# link_t.net
KiCad netlist of a schematic drawn in Altium Designer
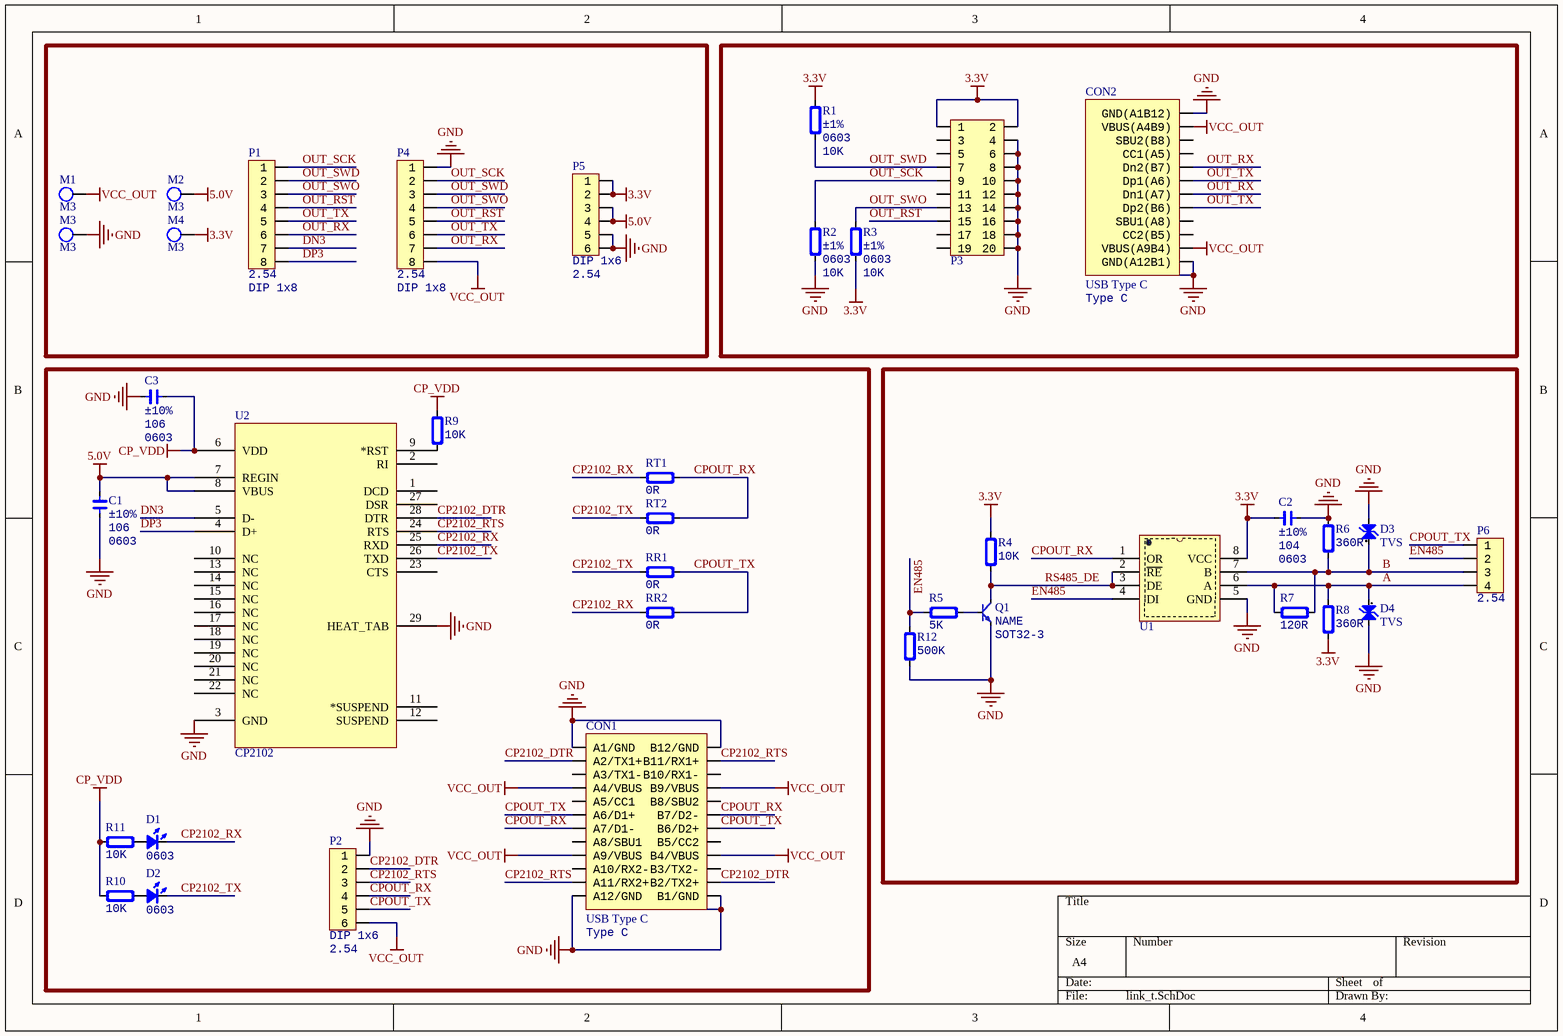
[diagram p0: link_t.SchDoc]

(export (version "E")
  (design (tool "Eeschema 10.0.6"))
  (components
    (comp (ref "C1")
      (value "106")
      (footprint "CAP_0603")
      (description "Capacitor")
      (fields (field (name "NOTE") "±10%") (field (name "TYPE") "0603") (field (name "Comment") "C0603"))
      (libsource (lib "") (part "Cap_0603_1"))
    )
    (comp (ref "C2")
      (value "104")
      (footprint "CAP_0603")
      (description "Capacitor")
      (fields (field (name "NOTE") "±10%") (field (name "TYPE") "0603") (field (name "Comment") "C0603"))
      (libsource (lib "") (part "Cap_0603_2"))
    )
    (comp (ref "C3")
      (value "106")
      (footprint "CAP_0603")
      (description "Capacitor")
      (fields (field (name "NOTE") "±10%") (field (name "TYPE") "0603") (field (name "Comment") "C0603"))
      (libsource (lib "Integrated_Library") (part "Cap_0603"))
    )
    (comp (ref "CON1")
      (value "USB Type C")
      (footprint "USB_TypeC_SMD_24P")
      (description "USB")
      (fields (field (name "ALTIUM_VALUE") "Type C"))
      (libsource (lib "Integrated_Library") (part "USB_TypeC"))
    )
    (comp (ref "CON2")
      (value "USB Type C")
      (footprint "USB_TypeC_SMD_16P")
      (description "USB")
      (fields (field (name "ALTIUM_VALUE") "Type C"))
      (libsource (lib "Integrated_Library") (part "USB_TypeC_16P"))
    )
    (comp (ref "D1")
      (value "D0603")
      (footprint "LED_0603_RED")
      (description "LED")
      (fields (field (name "TYPE") "0603"))
      (libsource (lib "Integrated_Library") (part "LED_0603"))
    )
    (comp (ref "D2")
      (value "D0603")
      (footprint "LED_0603_RED")
      (description "LED")
      (fields (field (name "TYPE") "0603"))
      (libsource (lib "Integrated_Library") (part "LED_0603"))
    )
    (comp (ref "D3")
      (value "TVS")
      (footprint "LED_0603_YELLOW")
      (description "静电保护二极管,VRWM=5V.IPP=9.4A")
      (libsource (lib "MxM_Library") (part "ESD LESD5D5.0CT1G"))
    )
    (comp (ref "D4")
      (value "TVS")
      (footprint "LED_0603_YELLOW")
      (description "静电保护二极管,VRWM=5V.IPP=9.4A")
      (libsource (lib "MxM_Library") (part "ESD LESD5D5.0CT1G"))
    )
    (comp (ref "M1")
      (value "M3")
      (footprint "M3")
      (description "M3 Nut")
      (libsource (lib "Integrated_Library") (part "M3"))
    )
    (comp (ref "M2")
      (value "M3")
      (footprint "M3")
      (description "M3 Nut")
      (libsource (lib "Integrated_Library") (part "M3"))
    )
    (comp (ref "M3")
      (value "M3")
      (footprint "M3")
      (description "M3 Nut")
      (libsource (lib "Integrated_Library") (part "M3"))
    )
    (comp (ref "M4")
      (value "M3")
      (footprint "M3")
      (description "M3 Nut")
      (libsource (lib "Integrated_Library") (part "M3"))
    )
    (comp (ref "P1")
      (value "2.54")
      (footprint "HDR1x8_TOP")
      (description "Header Top")
      (fields (field (name "TYPE") "DIP 1x8") (field (name "Comment") "HDR1x8"))
      (libsource (lib "Integrated_Library") (part "HDR1x8_2.54TOP"))
    )
    (comp (ref "P2")
      (value "2.54")
      (footprint "HDR1x6_TOP")
      (description "Header Top")
      (fields (field (name "TYPE") "DIP 1x6") (field (name "Comment") "HDR1x6"))
      (libsource (lib "Integrated_Library") (part "HDR1x6_2.54TOP"))
    )
    (comp (ref "P3")
      (value "HDR2x10")
      (footprint "PCB_Special:JN_STM_20PIN")
      (description "Header")
      (libsource (lib "Integrated_Library") (part "HDR2x10_2.54"))
    )
    (comp (ref "P4")
      (value "2.54")
      (footprint "HDR1X8_H")
      (description "Header Top")
      (fields (field (name "TYPE") "DIP 1x8") (field (name "Comment") "HDR1x8"))
      (libsource (lib "Integrated_Library") (part "HDR1x8_2.54TOP"))
    )
    (comp (ref "P5")
      (value "2.54")
      (footprint "HDR1x6_TOP")
      (description "Header Top")
      (fields (field (name "TYPE") "DIP 1x6") (field (name "Comment") "HDR1x6"))
      (libsource (lib "Integrated_Library") (part "HDR1x6_2.54TOP"))
    )
    (comp (ref "P6")
      (value "2.54")
      (footprint "HDR1x4_TOP")
      (description "Header Top")
      (fields (field (name "Comment") "HDR1x4"))
      (libsource (lib "Integrated_Library") (part "HDR1x4_2.54TOP"))
    )
    (comp (ref "Q1")
      (value "NAME")
      (footprint "SOT23-3")
      (description "Transistor")
      (fields (field (name "TYPE") "SOT32-3"))
      (libsource (lib "Integrated_Library") (part "BJT_NPN"))
    )
    (comp (ref "R1")
      (value "10K")
      (footprint "RES_0603")
      (description "Resistor")
      (fields (field (name "NOTE") "±1%") (field (name "TYPE") "0603") (field (name "Comment") "R0603"))
      (libsource (lib "Integrated_Library") (part "Res_0603"))
    )
    (comp (ref "R2")
      (value "10K")
      (footprint "RES_0603")
      (description "Resistor")
      (fields (field (name "NOTE") "±1%") (field (name "TYPE") "0603") (field (name "Comment") "R0603"))
      (libsource (lib "Integrated_Library") (part "Res_0603"))
    )
    (comp (ref "R3")
      (value "10K")
      (footprint "RES_0603")
      (description "Resistor")
      (fields (field (name "NOTE") "±1%") (field (name "TYPE") "0603") (field (name "Comment") "R0603"))
      (libsource (lib "Integrated_Library") (part "Res_0603"))
    )
    (comp (ref "R4")
      (value "10K")
      (footprint "RES_0603")
      (description "Resistor")
      (fields (field (name "Comment") "R0603"))
      (libsource (lib "Integrated_Library") (part "Res_0603"))
    )
    (comp (ref "R5")
      (value "5K")
      (footprint "RES_0603")
      (description "Resistor")
      (fields (field (name "Comment") "R0603"))
      (libsource (lib "Integrated_Library") (part "Res_0603"))
    )
    (comp (ref "R6")
      (value "360R")
      (footprint "RES_0603")
      (description "Resistor")
      (fields (field (name "Comment") "R0603"))
      (libsource (lib "Integrated_Library") (part "Res_0603"))
    )
    (comp (ref "R7")
      (value "120R")
      (footprint "RES_0603")
      (description "Resistor")
      (fields (field (name "Comment") "R0603"))
      (libsource (lib "Integrated_Library") (part "Res_0603"))
    )
    (comp (ref "R8")
      (value "360R")
      (footprint "RES_0603")
      (description "Resistor")
      (fields (field (name "Comment") "R0603"))
      (libsource (lib "Integrated_Library") (part "Res_0603"))
    )
    (comp (ref "R9")
      (value "10K")
      (footprint "RES_0603")
      (description "Resistor")
      (fields (field (name "Comment") "R0603"))
      (libsource (lib "Integrated_Library") (part "Res_0603"))
    )
    (comp (ref "R10")
      (value "10K")
      (footprint "RES_0603")
      (description "Resistor")
      (fields (field (name "Comment") "R0603"))
      (libsource (lib "Integrated_Library") (part "Res_0603"))
    )
    (comp (ref "R11")
      (value "10K")
      (footprint "RES_0603")
      (description "Resistor")
      (fields (field (name "Comment") "R0603"))
      (libsource (lib "Integrated_Library") (part "Res_0603"))
    )
    (comp (ref "R12")
      (value "500K")
      (footprint "RES_0603")
      (description "Resistor")
      (fields (field (name "Comment") "R0603"))
      (libsource (lib "Integrated_Library") (part "Res_0603"))
    )
    (comp (ref "RR1")
      (value "0R")
      (footprint "RES_0603")
      (description "Resistor")
      (fields (field (name "Comment") "R0603"))
      (libsource (lib "Integrated_Library") (part "Res_0603"))
    )
    (comp (ref "RR2")
      (value "0R")
      (footprint "RES_0603")
      (description "Resistor")
      (fields (field (name "Comment") "R0603"))
      (libsource (lib "Integrated_Library") (part "Res_0603"))
    )
    (comp (ref "RT1")
      (value "0R")
      (footprint "RES_0603")
      (description "Resistor")
      (fields (field (name "Comment") "R0603"))
      (libsource (lib "Integrated_Library") (part "Res_0603"))
    )
    (comp (ref "RT2")
      (value "0R")
      (footprint "RES_0603")
      (description "Resistor")
      (fields (field (name "Comment") "R0603"))
      (libsource (lib "Integrated_Library") (part "Res_0603"))
    )
    (comp (ref "U1")
      (value "SP3485")
      (footprint "SOP8")
      (description "半双工收发器")
      (libsource (lib "MxM_Library") (part "SP3485"))
    )
    (comp (ref "U2")
      (value "CP2102")
      (footprint "rice_mill_esp32:QFN-28")
      (description "USB转TTL")
      (libsource (lib "mLib") (part "CP2102"))
    )
  )
  (nets
    (net (code "1") (name "/A") (class "Default")
      (node (ref "D4") (pin "1") (pinfunction "A_1") (pintype "passive"))
      (node (ref "P6") (pin "4") (pinfunction "4_4") (pintype "passive"))
      (node (ref "R7") (pin "1") (pinfunction "1_1") (pintype "passive"))
      (node (ref "R8") (pin "2") (pinfunction "2_2") (pintype "passive"))
      (node (ref "U1") (pin "6") (pinfunction "A_6") (pintype "passive"))
    )
    (net (code "2") (name "/B") (class "Default")
      (node (ref "D3") (pin "1") (pinfunction "A_1") (pintype "passive"))
      (node (ref "P6") (pin "3") (pinfunction "3_3") (pintype "passive"))
      (node (ref "R6") (pin "1") (pinfunction "1_1") (pintype "passive"))
      (node (ref "R7") (pin "2") (pinfunction "2_2") (pintype "passive"))
      (node (ref "U1") (pin "7") (pinfunction "B_7") (pintype "passive"))
    )
    (net (code "3") (name "/CP2102_DTR") (class "Default")
      (node (ref "CON1") (pin "A2") (pinfunction "A2/TX1+_A2") (pintype "passive"))
      (node (ref "CON1") (pin "B2") (pinfunction "B2/TX2+_B2") (pintype "passive"))
      (node (ref "P2") (pin "2") (pinfunction "2_2") (pintype "passive"))
      (node (ref "U2") (pin "28") (pinfunction "DTR_28") (pintype "passive"))
    )
    (net (code "4") (name "/CP2102_RTS") (class "Default")
      (node (ref "CON1") (pin "A11") (pinfunction "A11/RX2+_A11") (pintype "passive"))
      (node (ref "CON1") (pin "B11") (pinfunction "B11/RX1+_B11") (pintype "passive"))
      (node (ref "P2") (pin "3") (pinfunction "3_3") (pintype "passive"))
      (node (ref "U2") (pin "24") (pinfunction "RTS_24") (pintype "passive"))
    )
    (net (code "5") (name "/CP2102_RX") (class "Default")
      (node (ref "D1") (pin "2") (pinfunction "K_2") (pintype "passive"))
      (node (ref "RR2") (pin "2") (pinfunction "2_2") (pintype "passive"))
      (node (ref "RT1") (pin "2") (pinfunction "2_2") (pintype "passive"))
      (node (ref "U2") (pin "25") (pinfunction "RXD_25") (pintype "passive"))
    )
    (net (code "6") (name "/CP2102_TX") (class "Default")
      (node (ref "D2") (pin "2") (pinfunction "K_2") (pintype "passive"))
      (node (ref "RR1") (pin "2") (pinfunction "2_2") (pintype "passive"))
      (node (ref "RT2") (pin "2") (pinfunction "2_2") (pintype "passive"))
      (node (ref "U2") (pin "26") (pinfunction "TXD_26") (pintype "passive"))
    )
    (net (code "7") (name "/CPOUT_RX") (class "Default")
      (node (ref "CON1") (pin "A7") (pinfunction "A7/D1-_A7") (pintype "passive"))
      (node (ref "CON1") (pin "B7") (pinfunction "B7/D2-_B7") (pintype "passive"))
      (node (ref "P2") (pin "4") (pinfunction "4_4") (pintype "passive"))
      (node (ref "RT1") (pin "1") (pinfunction "1_1") (pintype "passive"))
      (node (ref "RT2") (pin "1") (pinfunction "1_1") (pintype "passive"))
      (node (ref "U1") (pin "1") (pinfunction "OR_1") (pintype "passive"))
    )
    (net (code "8") (name "/CPOUT_TX") (class "Default")
      (node (ref "CON1") (pin "A6") (pinfunction "A6/D1+_A6") (pintype "passive"))
      (node (ref "CON1") (pin "B6") (pinfunction "B6/D2+_B6") (pintype "passive"))
      (node (ref "P2") (pin "5") (pinfunction "5_5") (pintype "passive"))
      (node (ref "P6") (pin "1") (pinfunction "1_1") (pintype "passive"))
      (node (ref "RR1") (pin "1") (pinfunction "1_1") (pintype "passive"))
      (node (ref "RR2") (pin "1") (pinfunction "1_1") (pintype "passive"))
    )
    (net (code "9") (name "/DN3") (class "Default")
      (node (ref "P1") (pin "7") (pinfunction "7_7") (pintype "passive"))
      (node (ref "U2") (pin "5") (pinfunction "D-_5") (pintype "passive"))
    )
    (net (code "10") (name "/DP3") (class "Default")
      (node (ref "P1") (pin "8") (pinfunction "8_8") (pintype "passive"))
      (node (ref "U2") (pin "4") (pinfunction "D+_4") (pintype "passive"))
    )
    (net (code "11") (name "/EN485") (class "Default")
      (node (ref "P6") (pin "2") (pinfunction "2_2") (pintype "passive"))
      (node (ref "R12") (pin "1") (pinfunction "1_1") (pintype "passive"))
      (node (ref "R5") (pin "2") (pinfunction "2_2") (pintype "passive"))
      (node (ref "U1") (pin "4") (pinfunction "DI_4") (pintype "passive"))
    )
    (net (code "12") (name "/OUT_RST") (class "Default")
      (node (ref "P1") (pin "4") (pinfunction "4_4") (pintype "passive"))
      (node (ref "P3") (pin "15") (pinfunction "15_15") (pintype "passive"))
      (node (ref "P4") (pin "5") (pinfunction "5_5") (pintype "passive"))
    )
    (net (code "13") (name "/OUT_RX") (class "Default")
      (node (ref "CON2") (pin "A7") (pinfunction "Dn1(A7)_A7") (pintype "passive"))
      (node (ref "CON2") (pin "B7") (pinfunction "Dn2(B7)_B7") (pintype "passive"))
      (node (ref "P1") (pin "6") (pinfunction "6_6") (pintype "passive"))
      (node (ref "P4") (pin "7") (pinfunction "7_7") (pintype "passive"))
    )
    (net (code "14") (name "/OUT_SCK") (class "Default")
      (node (ref "P1") (pin "1") (pinfunction "1_1") (pintype "passive"))
      (node (ref "P3") (pin "9") (pinfunction "9_9") (pintype "passive"))
      (node (ref "P4") (pin "2") (pinfunction "2_2") (pintype "passive"))
      (node (ref "R2") (pin "2") (pinfunction "2_2") (pintype "passive"))
    )
    (net (code "15") (name "/OUT_SWD") (class "Default")
      (node (ref "P1") (pin "2") (pinfunction "2_2") (pintype "passive"))
      (node (ref "P3") (pin "7") (pinfunction "7_7") (pintype "passive"))
      (node (ref "P4") (pin "3") (pinfunction "3_3") (pintype "passive"))
      (node (ref "R1") (pin "2") (pinfunction "2_2") (pintype "passive"))
    )
    (net (code "16") (name "/OUT_SWO") (class "Default")
      (node (ref "P1") (pin "3") (pinfunction "3_3") (pintype "passive"))
      (node (ref "P3") (pin "13") (pinfunction "13_13") (pintype "passive"))
      (node (ref "P4") (pin "4") (pinfunction "4_4") (pintype "passive"))
      (node (ref "R3") (pin "2") (pinfunction "2_2") (pintype "passive"))
    )
    (net (code "17") (name "/OUT_TX") (class "Default")
      (node (ref "CON2") (pin "A6") (pinfunction "Dp1(A6)_A6") (pintype "passive"))
      (node (ref "CON2") (pin "B6") (pinfunction "Dp2(B6)_B6") (pintype "passive"))
      (node (ref "P1") (pin "5") (pinfunction "5_5") (pintype "passive"))
      (node (ref "P4") (pin "6") (pinfunction "6_6") (pintype "passive"))
    )
    (net (code "18") (name "/RS485_DE") (class "Default")
      (node (ref "Q1") (pin "3") (pinfunction "C_3") (pintype "passive"))
      (node (ref "R4") (pin "2") (pinfunction "2_2") (pintype "passive"))
      (node (ref "U1") (pin "2") (pinfunction "~{RE}_2") (pintype "passive"))
      (node (ref "U1") (pin "3") (pinfunction "DE_3") (pintype "passive"))
    )
    (net (code "19") (name "3.3V") (class "Default")
      (node (ref "C2") (pin "2") (pinfunction "2_2") (pintype "passive"))
      (node (ref "M4") (pin "1") (pinfunction "1_1") (pintype "passive"))
      (node (ref "P3") (pin "1") (pinfunction "1_1") (pintype "passive"))
      (node (ref "P3") (pin "2") (pinfunction "2_2") (pintype "passive"))
      (node (ref "P5") (pin "1") (pinfunction "1_1") (pintype "passive"))
      (node (ref "P5") (pin "2") (pinfunction "2_2") (pintype "passive"))
      (node (ref "R1") (pin "1") (pinfunction "1_1") (pintype "passive"))
      (node (ref "R3") (pin "1") (pinfunction "1_1") (pintype "passive"))
      (node (ref "R4") (pin "1") (pinfunction "1_1") (pintype "passive"))
      (node (ref "R8") (pin "1") (pinfunction "1_1") (pintype "passive"))
      (node (ref "U1") (pin "8") (pinfunction "VCC_8") (pintype "passive"))
    )
    (net (code "20") (name "5.0V") (class "Default")
      (node (ref "C1") (pin "2") (pinfunction "2_2") (pintype "passive"))
      (node (ref "M2") (pin "1") (pinfunction "1_1") (pintype "passive"))
      (node (ref "P5") (pin "3") (pinfunction "3_3") (pintype "passive"))
      (node (ref "P5") (pin "4") (pinfunction "4_4") (pintype "passive"))
      (node (ref "U2") (pin "7") (pinfunction "REGIN_7") (pintype "passive"))
      (node (ref "U2") (pin "8") (pinfunction "VBUS_8") (pintype "passive"))
    )
    (net (code "21") (name "CP_VDD") (class "Default")
      (node (ref "C3") (pin "2") (pinfunction "2_2") (pintype "passive"))
      (node (ref "R10") (pin "1") (pinfunction "1_1") (pintype "passive"))
      (node (ref "R11") (pin "1") (pinfunction "1_1") (pintype "passive"))
      (node (ref "R9") (pin "2") (pinfunction "2_2") (pintype "passive"))
      (node (ref "U2") (pin "6") (pinfunction "VDD_6") (pintype "passive"))
    )
    (net (code "22") (name "GND") (class "Default")
      (node (ref "C1") (pin "1") (pinfunction "1_1") (pintype "passive"))
      (node (ref "C2") (pin "1") (pinfunction "1_1") (pintype "passive"))
      (node (ref "C3") (pin "1") (pinfunction "1_1") (pintype "passive"))
      (node (ref "CON1") (pin "0") (pinfunction "SH_0") (pintype "passive"))
      (node (ref "CON1") (pin "A1") (pinfunction "A1/GND_A1") (pintype "passive"))
      (node (ref "CON1") (pin "A12") (pinfunction "A12/GND_A12") (pintype "passive"))
      (node (ref "CON1") (pin "B1") (pinfunction "B1/GND_B1") (pintype "passive"))
      (node (ref "CON1") (pin "B12") (pinfunction "B12/GND_B12") (pintype "passive"))
      (node (ref "CON2") (pin "0") (pinfunction "SH_0") (pintype "passive"))
      (node (ref "CON2") (pin "A12B1") (pinfunction "GND(A12B1)_A12B1") (pintype "passive"))
      (node (ref "CON2") (pin "A1B12") (pinfunction "GND(A1B12)_A1B12") (pintype "passive"))
      (node (ref "D3") (pin "2") (pinfunction "K_2") (pintype "passive"))
      (node (ref "D4") (pin "2") (pinfunction "K_2") (pintype "passive"))
      (node (ref "M3") (pin "1") (pinfunction "1_1") (pintype "passive"))
      (node (ref "P2") (pin "1") (pinfunction "1_1") (pintype "passive"))
      (node (ref "P3") (pin "10") (pinfunction "10_10") (pintype "passive"))
      (node (ref "P3") (pin "12") (pinfunction "12_12") (pintype "passive"))
      (node (ref "P3") (pin "14") (pinfunction "14_14") (pintype "passive"))
      (node (ref "P3") (pin "16") (pinfunction "16_16") (pintype "passive"))
      (node (ref "P3") (pin "18") (pinfunction "18_18") (pintype "passive"))
      (node (ref "P3") (pin "20") (pinfunction "20_20") (pintype "passive"))
      (node (ref "P3") (pin "4") (pinfunction "4_4") (pintype "passive"))
      (node (ref "P3") (pin "6") (pinfunction "6_6") (pintype "passive"))
      (node (ref "P3") (pin "8") (pinfunction "8_8") (pintype "passive"))
      (node (ref "P4") (pin "1") (pinfunction "1_1") (pintype "passive"))
      (node (ref "P5") (pin "5") (pinfunction "5_5") (pintype "passive"))
      (node (ref "P5") (pin "6") (pinfunction "6_6") (pintype "passive"))
      (node (ref "Q1") (pin "2") (pinfunction "E_2") (pintype "passive"))
      (node (ref "R12") (pin "2") (pinfunction "2_2") (pintype "passive"))
      (node (ref "R2") (pin "1") (pinfunction "1_1") (pintype "passive"))
      (node (ref "R6") (pin "2") (pinfunction "2_2") (pintype "passive"))
      (node (ref "U1") (pin "5") (pinfunction "GND_5") (pintype "passive"))
      (node (ref "U2") (pin "29") (pinfunction "HEAT_TAB_29") (pintype "passive"))
      (node (ref "U2") (pin "3") (pinfunction "GND_3") (pintype "passive"))
    )
    (net (code "23") (name "Net-(D1-A)") (class "Default")
      (node (ref "D1") (pin "1") (pinfunction "A_1") (pintype "passive"))
      (node (ref "R11") (pin "2") (pinfunction "2_2") (pintype "passive"))
    )
    (net (code "24") (name "Net-(D2-A)") (class "Default")
      (node (ref "D2") (pin "1") (pinfunction "A_1") (pintype "passive"))
      (node (ref "R10") (pin "2") (pinfunction "2_2") (pintype "passive"))
    )
    (net (code "25") (name "Net-(Q1-B)") (class "Default")
      (node (ref "Q1") (pin "1") (pinfunction "B_1") (pintype "passive"))
      (node (ref "R5") (pin "1") (pinfunction "1_1") (pintype "passive"))
    )
    (net (code "26") (name "Net-(U2-*RST)") (class "Default")
      (node (ref "R9") (pin "1") (pinfunction "1_1") (pintype "passive"))
      (node (ref "U2") (pin "9") (pinfunction "*RST_9") (pintype "passive"))
    )
    (net (code "27") (name "VCC_OUT") (class "Default")
      (node (ref "CON1") (pin "A4") (pinfunction "A4/VBUS_A4") (pintype "passive"))
      (node (ref "CON1") (pin "A9") (pinfunction "A9/VBUS_A9") (pintype "passive"))
      (node (ref "CON1") (pin "B4") (pinfunction "B4/VBUS_B4") (pintype "passive"))
      (node (ref "CON1") (pin "B9") (pinfunction "B9/VBUS_B9") (pintype "passive"))
      (node (ref "CON2") (pin "A4B9") (pinfunction "VBUS(A4B9)_A4B9") (pintype "passive"))
      (node (ref "CON2") (pin "A9B4") (pinfunction "VBUS(A9B4)_A9B4") (pintype "passive"))
      (node (ref "M1") (pin "1") (pinfunction "1_1") (pintype "passive"))
      (node (ref "P2") (pin "6") (pinfunction "6_6") (pintype "passive"))
      (node (ref "P4") (pin "8") (pinfunction "8_8") (pintype "passive"))
    )
    (net (code "28") (name "unconnected-(CON1-A3{slash}TX1--PadA3)") (class "Default")
      (node (ref "CON1") (pin "A3") (pinfunction "A3/TX1-_A3") (pintype "passive"))
    )
    (net (code "29") (name "unconnected-(CON1-A5{slash}CC1-PadA5)") (class "Default")
      (node (ref "CON1") (pin "A5") (pinfunction "A5/CC1_A5") (pintype "passive"))
    )
    (net (code "30") (name "unconnected-(CON1-A8{slash}SBU1-PadA8)") (class "Default")
      (node (ref "CON1") (pin "A8") (pinfunction "A8/SBU1_A8") (pintype "passive"))
    )
    (net (code "31") (name "unconnected-(CON1-A10{slash}RX2--PadA10)") (class "Default")
      (node (ref "CON1") (pin "A10") (pinfunction "A10/RX2-_A10") (pintype "passive"))
    )
    (net (code "32") (name "unconnected-(CON1-B3{slash}TX2--PadB3)") (class "Default")
      (node (ref "CON1") (pin "B3") (pinfunction "B3/TX2-_B3") (pintype "passive"))
    )
    (net (code "33") (name "unconnected-(CON1-B5{slash}CC2-PadB5)") (class "Default")
      (node (ref "CON1") (pin "B5") (pinfunction "B5/CC2_B5") (pintype "passive"))
    )
    (net (code "34") (name "unconnected-(CON1-B8{slash}SBU2-PadB8)") (class "Default")
      (node (ref "CON1") (pin "B8") (pinfunction "B8/SBU2_B8") (pintype "passive"))
    )
    (net (code "35") (name "unconnected-(CON1-B10{slash}RX1--PadB10)") (class "Default")
      (node (ref "CON1") (pin "B10") (pinfunction "B10/RX1-_B10") (pintype "passive"))
    )
    (net (code "36") (name "unconnected-(CON2-CC1(A5)-PadA5)") (class "Default")
      (node (ref "CON2") (pin "A5") (pinfunction "CC1(A5)_A5") (pintype "passive"))
    )
    (net (code "37") (name "unconnected-(CON2-CC2(B5)-PadB5)") (class "Default")
      (node (ref "CON2") (pin "B5") (pinfunction "CC2(B5)_B5") (pintype "passive"))
    )
    (net (code "38") (name "unconnected-(CON2-SBU1(A8)-PadA8)") (class "Default")
      (node (ref "CON2") (pin "A8") (pinfunction "SBU1(A8)_A8") (pintype "passive"))
    )
    (net (code "39") (name "unconnected-(CON2-SBU2(B8)-PadB8)") (class "Default")
      (node (ref "CON2") (pin "B8") (pinfunction "SBU2(B8)_B8") (pintype "passive"))
    )
    (net (code "40") (name "unconnected-(P3-Pad3)") (class "Default")
      (node (ref "P3") (pin "3") (pinfunction "3_3") (pintype "passive"))
    )
    (net (code "41") (name "unconnected-(P3-Pad5)") (class "Default")
      (node (ref "P3") (pin "5") (pinfunction "5_5") (pintype "passive"))
    )
    (net (code "42") (name "unconnected-(P3-Pad11)") (class "Default")
      (node (ref "P3") (pin "11") (pinfunction "11_11") (pintype "passive"))
    )
    (net (code "43") (name "unconnected-(P3-Pad17)") (class "Default")
      (node (ref "P3") (pin "17") (pinfunction "17_17") (pintype "passive"))
    )
    (net (code "44") (name "unconnected-(P3-Pad19)") (class "Default")
      (node (ref "P3") (pin "19") (pinfunction "19_19") (pintype "passive"))
    )
    (net (code "45") (name "unconnected-(U2-*SUSPEND-Pad11)") (class "Default")
      (node (ref "U2") (pin "11") (pinfunction "*SUSPEND_11") (pintype "passive"))
    )
    (net (code "46") (name "unconnected-(U2-CTS-Pad23)") (class "Default")
      (node (ref "U2") (pin "23") (pinfunction "CTS_23") (pintype "passive"))
    )
    (net (code "47") (name "unconnected-(U2-DCD-Pad1)") (class "Default")
      (node (ref "U2") (pin "1") (pinfunction "DCD_1") (pintype "passive"))
    )
    (net (code "48") (name "unconnected-(U2-DSR-Pad27)") (class "Default")
      (node (ref "U2") (pin "27") (pinfunction "DSR_27") (pintype "passive"))
    )
    (net (code "49") (name "unconnected-(U2-NC-Pad10)") (class "Default")
      (node (ref "U2") (pin "10") (pinfunction "NC_10") (pintype "passive"))
    )
    (net (code "50") (name "unconnected-(U2-NC-Pad13)") (class "Default")
      (node (ref "U2") (pin "13") (pinfunction "NC_13") (pintype "passive"))
    )
    (net (code "51") (name "unconnected-(U2-NC-Pad14)") (class "Default")
      (node (ref "U2") (pin "14") (pinfunction "NC_14") (pintype "passive"))
    )
    (net (code "52") (name "unconnected-(U2-NC-Pad15)") (class "Default")
      (node (ref "U2") (pin "15") (pinfunction "NC_15") (pintype "passive"))
    )
    (net (code "53") (name "unconnected-(U2-NC-Pad16)") (class "Default")
      (node (ref "U2") (pin "16") (pinfunction "NC_16") (pintype "passive"))
    )
    (net (code "54") (name "unconnected-(U2-NC-Pad17)") (class "Default")
      (node (ref "U2") (pin "17") (pinfunction "NC_17") (pintype "passive"))
    )
    (net (code "55") (name "unconnected-(U2-NC-Pad18)") (class "Default")
      (node (ref "U2") (pin "18") (pinfunction "NC_18") (pintype "passive"))
    )
    (net (code "56") (name "unconnected-(U2-NC-Pad19)") (class "Default")
      (node (ref "U2") (pin "19") (pinfunction "NC_19") (pintype "passive"))
    )
    (net (code "57") (name "unconnected-(U2-NC-Pad20)") (class "Default")
      (node (ref "U2") (pin "20") (pinfunction "NC_20") (pintype "passive"))
    )
    (net (code "58") (name "unconnected-(U2-NC-Pad21)") (class "Default")
      (node (ref "U2") (pin "21") (pinfunction "NC_21") (pintype "passive"))
    )
    (net (code "59") (name "unconnected-(U2-NC-Pad22)") (class "Default")
      (node (ref "U2") (pin "22") (pinfunction "NC_22") (pintype "passive"))
    )
    (net (code "60") (name "unconnected-(U2-RI-Pad2)") (class "Default")
      (node (ref "U2") (pin "2") (pinfunction "RI_2") (pintype "passive"))
    )
    (net (code "61") (name "unconnected-(U2-SUSPEND-Pad12)") (class "Default")
      (node (ref "U2") (pin "12") (pinfunction "SUSPEND_12") (pintype "passive"))
    )
  )
)
